# ACE.net
KiCad netlist of a schematic drawn in Altium Designer
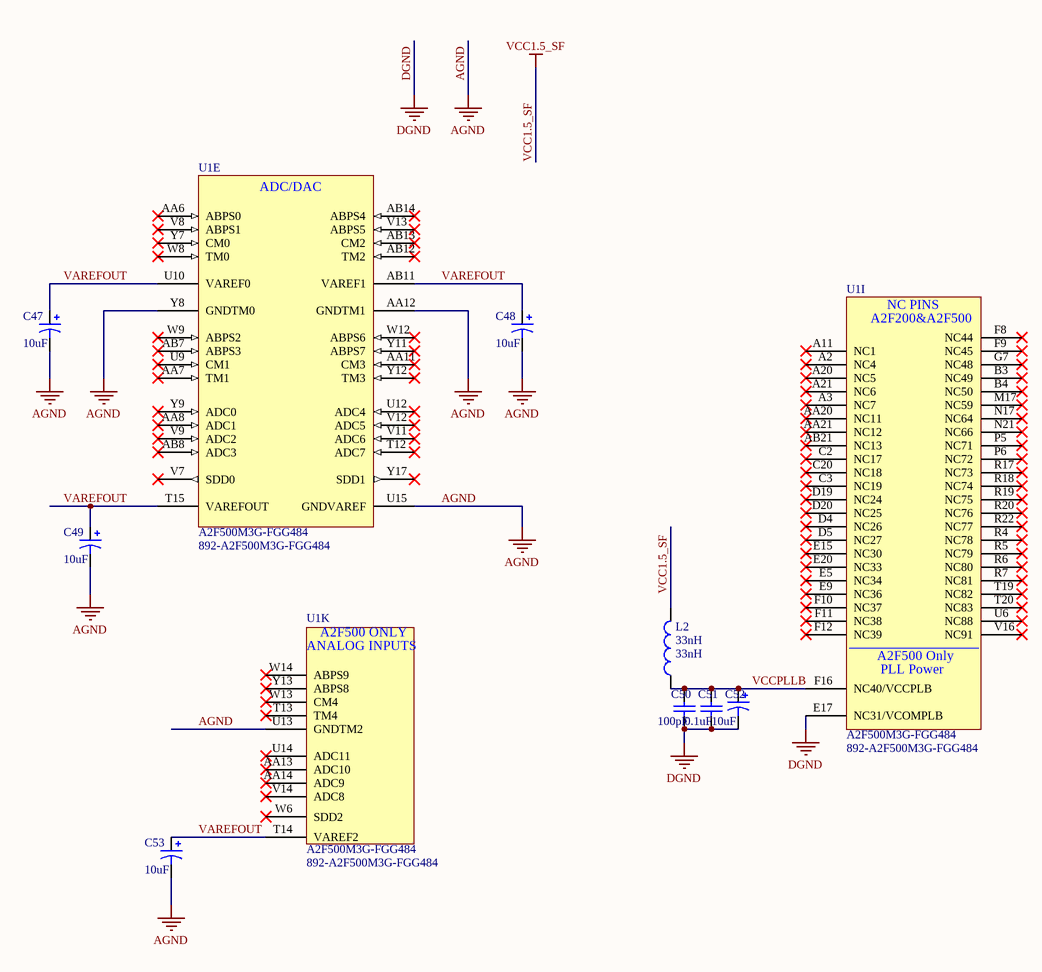
[diagram p0: ACE.SchDoc]

(export (version "E")
  (design (tool "Eeschema 10.0.6"))
  (components
    (comp (ref "C47")
      (value "10uF")
      (footprint "C0805")
      (description "Polarized Capacitor (Surface Mount)")
      (fields (field (name "PUBLISHER") "Altium Limited"))
      (libsource (lib "Miscellaneous Devices") (part "Cap Pol3"))
    )
    (comp (ref "C48")
      (value "10uF")
      (footprint "C0805")
      (description "Polarized Capacitor (Surface Mount)")
      (fields (field (name "PUBLISHER") "Altium Limited"))
      (libsource (lib "Miscellaneous Devices") (part "Cap Pol3"))
    )
    (comp (ref "C49")
      (value "10uF")
      (footprint "C0805")
      (description "Polarized Capacitor (Surface Mount)")
      (fields (field (name "PUBLISHER") "Altium Limited"))
      (libsource (lib "Miscellaneous Devices") (part "Cap Pol3"))
    )
    (comp (ref "C50")
      (value "100pF")
      (footprint "0402")
      (description "Capacitor (Semiconductor SIM Model)")
      (fields (field (name "PUBLISHER") "Altium Limited"))
      (libsource (lib "Miscellaneous Devices") (part "Cap Semi"))
    )
    (comp (ref "C51")
      (value "0.1uF")
      (footprint "0402")
      (description "Capacitor (Semiconductor SIM Model)")
      (fields (field (name "PUBLISHER") "Altium Limited"))
      (libsource (lib "Miscellaneous Devices") (part "Cap Semi"))
    )
    (comp (ref "C52")
      (value "10uF")
      (footprint "C0805")
      (description "Polarized Capacitor (Surface Mount)")
      (fields (field (name "PUBLISHER") "Altium Limited"))
      (libsource (lib "Miscellaneous Devices") (part "Cap Pol3"))
    )
    (comp (ref "C53")
      (value "10uF")
      (footprint "C0805")
      (description "Polarized Capacitor (Surface Mount)")
      (fields (field (name "PUBLISHER") "Altium Limited"))
      (libsource (lib "Miscellaneous Devices") (part "Cap Pol3"))
    )
    (comp (ref "L2")
      (value "33nH")
      (footprint "0402")
      (description "Inductor")
      (fields (field (name "ALTIUM_VALUE") "33nH") (field (name "PUBLISHER") "Altium Limited"))
      (libsource (lib "Miscellaneous Devices") (part "Inductor"))
    )
    (comp (ref "U1")
      (value "A2F500M3G-FGG484")
      (footprint "BGA100P22X22-484N")
      (description "FPGA - Field Programmable Gate Array 500K System Gates")
      (fields (field (name "SUPPLIER PART NUMBER 1") "892-A2F500M3G-FGG484"))
      (libsource (lib "SDR") (part "F2-200_500-FGG484_1"))
    )
  )
  (nets
    (net (code "1") (name "/VAREFOUT") (class "Default")
      (node (ref "C47") (pin "1") (pinfunction "1_1") (pintype "passive"))
      (node (ref "C48") (pin "1") (pinfunction "1_1") (pintype "passive"))
      (node (ref "C49") (pin "1") (pinfunction "1_1") (pintype "passive"))
      (node (ref "C53") (pin "1") (pinfunction "1_1") (pintype "passive"))
      (node (ref "U1") (pin "AB11") (pinfunction "VAREF1_AB11") (pintype "power_in"))
      (node (ref "U1") (pin "T14") (pinfunction "VAREF2_T14") (pintype "power_in"))
      (node (ref "U1") (pin "T15") (pinfunction "VAREFOUT_T15") (pintype "power_in"))
      (node (ref "U1") (pin "U10") (pinfunction "VAREF0_U10") (pintype "power_in"))
    )
    (net (code "2") (name "/VCCPLLB") (class "Default")
      (node (ref "C50") (pin "2") (pinfunction "2_2") (pintype "passive"))
      (node (ref "C51") (pin "2") (pinfunction "2_2") (pintype "passive"))
      (node (ref "C52") (pin "1") (pinfunction "1_1") (pintype "passive"))
      (node (ref "L2") (pin "1") (pinfunction "1_1") (pintype "passive"))
      (node (ref "U1") (pin "F16") (pinfunction "NC40/VCCPLB_F16") (pintype "power_in"))
    )
    (net (code "3") (name "AGND") (class "Default")
      (node (ref "C47") (pin "2") (pinfunction "2_2") (pintype "passive"))
      (node (ref "C48") (pin "2") (pinfunction "2_2") (pintype "passive"))
      (node (ref "C49") (pin "2") (pinfunction "2_2") (pintype "passive"))
      (node (ref "C53") (pin "2") (pinfunction "2_2") (pintype "passive"))
      (node (ref "U1") (pin "AA12") (pinfunction "GNDTM1_AA12") (pintype "power_in"))
      (node (ref "U1") (pin "U13") (pinfunction "GNDTM2_U13") (pintype "passive"))
      (node (ref "U1") (pin "U15") (pinfunction "GNDVAREF_U15") (pintype "power_in"))
      (node (ref "U1") (pin "Y8") (pinfunction "GNDTM0_Y8") (pintype "power_in"))
    )
    (net (code "4") (name "DGND") (class "Default")
      (node (ref "C50") (pin "1") (pinfunction "1_1") (pintype "passive"))
      (node (ref "C51") (pin "1") (pinfunction "1_1") (pintype "passive"))
      (node (ref "C52") (pin "2") (pinfunction "2_2") (pintype "passive"))
      (node (ref "U1") (pin "E17") (pinfunction "NC31/VCOMPLB_E17") (pintype "power_in"))
    )
    (net (code "5") (name "VCC1.5_SF") (class "Default")
      (node (ref "L2") (pin "2") (pinfunction "2_2") (pintype "passive"))
    )
    (net (code "6") (name "unconnected-(U1E-ABPS0-PadAA6)") (class "Default")
      (node (ref "U1") (pin "AA6") (pinfunction "ABPS0_AA6") (pintype "input+no_connect"))
    )
    (net (code "7") (name "unconnected-(U1E-ABPS1-PadV8)") (class "Default")
      (node (ref "U1") (pin "V8") (pinfunction "ABPS1_V8") (pintype "input+no_connect"))
    )
    (net (code "8") (name "unconnected-(U1E-ABPS2-PadW9)") (class "Default")
      (node (ref "U1") (pin "W9") (pinfunction "ABPS2_W9") (pintype "input+no_connect"))
    )
    (net (code "9") (name "unconnected-(U1E-ABPS3-PadAB7)") (class "Default")
      (node (ref "U1") (pin "AB7") (pinfunction "ABPS3_AB7") (pintype "input+no_connect"))
    )
    (net (code "10") (name "unconnected-(U1E-ABPS4-PadAB14)") (class "Default")
      (node (ref "U1") (pin "AB14") (pinfunction "ABPS4_AB14") (pintype "input+no_connect"))
    )
    (net (code "11") (name "unconnected-(U1E-ABPS5-PadV13)") (class "Default")
      (node (ref "U1") (pin "V13") (pinfunction "ABPS5_V13") (pintype "input+no_connect"))
    )
    (net (code "12") (name "unconnected-(U1E-ABPS6-PadW12)") (class "Default")
      (node (ref "U1") (pin "W12") (pinfunction "ABPS6_W12") (pintype "input+no_connect"))
    )
    (net (code "13") (name "unconnected-(U1E-ABPS7-PadY11)") (class "Default")
      (node (ref "U1") (pin "Y11") (pinfunction "ABPS7_Y11") (pintype "input+no_connect"))
    )
    (net (code "14") (name "unconnected-(U1E-ADC0-PadY9)") (class "Default")
      (node (ref "U1") (pin "Y9") (pinfunction "ADC0_Y9") (pintype "input+no_connect"))
    )
    (net (code "15") (name "unconnected-(U1E-ADC1-PadAA8)") (class "Default")
      (node (ref "U1") (pin "AA8") (pinfunction "ADC1_AA8") (pintype "input+no_connect"))
    )
    (net (code "16") (name "unconnected-(U1E-ADC2-PadV9)") (class "Default")
      (node (ref "U1") (pin "V9") (pinfunction "ADC2_V9") (pintype "input+no_connect"))
    )
    (net (code "17") (name "unconnected-(U1E-ADC3-PadAB8)") (class "Default")
      (node (ref "U1") (pin "AB8") (pinfunction "ADC3_AB8") (pintype "input+no_connect"))
    )
    (net (code "18") (name "unconnected-(U1E-ADC4-PadU12)") (class "Default")
      (node (ref "U1") (pin "U12") (pinfunction "ADC4_U12") (pintype "input+no_connect"))
    )
    (net (code "19") (name "unconnected-(U1E-ADC5-PadV12)") (class "Default")
      (node (ref "U1") (pin "V12") (pinfunction "ADC5_V12") (pintype "input+no_connect"))
    )
    (net (code "20") (name "unconnected-(U1E-ADC6-PadV11)") (class "Default")
      (node (ref "U1") (pin "V11") (pinfunction "ADC6_V11") (pintype "input+no_connect"))
    )
    (net (code "21") (name "unconnected-(U1E-ADC7-PadT12)") (class "Default")
      (node (ref "U1") (pin "T12") (pinfunction "ADC7_T12") (pintype "input+no_connect"))
    )
    (net (code "22") (name "unconnected-(U1E-CM0-PadY7)") (class "Default")
      (node (ref "U1") (pin "Y7") (pinfunction "CM0_Y7") (pintype "input+no_connect"))
    )
    (net (code "23") (name "unconnected-(U1E-CM1-PadU9)") (class "Default")
      (node (ref "U1") (pin "U9") (pinfunction "CM1_U9") (pintype "input+no_connect"))
    )
    (net (code "24") (name "unconnected-(U1E-CM2-PadAB13)") (class "Default")
      (node (ref "U1") (pin "AB13") (pinfunction "CM2_AB13") (pintype "input+no_connect"))
    )
    (net (code "25") (name "unconnected-(U1E-CM3-PadAA11)") (class "Default")
      (node (ref "U1") (pin "AA11") (pinfunction "CM3_AA11") (pintype "input+no_connect"))
    )
    (net (code "26") (name "unconnected-(U1E-SDD0-PadV7)") (class "Default")
      (node (ref "U1") (pin "V7") (pinfunction "SDD0_V7") (pintype "output+no_connect"))
    )
    (net (code "27") (name "unconnected-(U1E-SDD1-PadY17)") (class "Default")
      (node (ref "U1") (pin "Y17") (pinfunction "SDD1_Y17") (pintype "output+no_connect"))
    )
    (net (code "28") (name "unconnected-(U1E-TM0-PadW8)") (class "Default")
      (node (ref "U1") (pin "W8") (pinfunction "TM0_W8") (pintype "input+no_connect"))
    )
    (net (code "29") (name "unconnected-(U1E-TM1-PadAA7)") (class "Default")
      (node (ref "U1") (pin "AA7") (pinfunction "TM1_AA7") (pintype "input+no_connect"))
    )
    (net (code "30") (name "unconnected-(U1E-TM2-PadAB12)") (class "Default")
      (node (ref "U1") (pin "AB12") (pinfunction "TM2_AB12") (pintype "input+no_connect"))
    )
    (net (code "31") (name "unconnected-(U1E-TM3-PadY12)") (class "Default")
      (node (ref "U1") (pin "Y12") (pinfunction "TM3_Y12") (pintype "input+no_connect"))
    )
    (net (code "32") (name "unconnected-(U1I-NC1-PadA11)") (class "Default")
      (node (ref "U1") (pin "A11") (pinfunction "NC1_A11") (pintype "passive+no_connect"))
    )
    (net (code "33") (name "unconnected-(U1I-NC4-PadA2)") (class "Default")
      (node (ref "U1") (pin "A2") (pinfunction "NC4_A2") (pintype "passive+no_connect"))
    )
    (net (code "34") (name "unconnected-(U1I-NC5-PadA20)") (class "Default")
      (node (ref "U1") (pin "A20") (pinfunction "NC5_A20") (pintype "passive+no_connect"))
    )
    (net (code "35") (name "unconnected-(U1I-NC6-PadA21)") (class "Default")
      (node (ref "U1") (pin "A21") (pinfunction "NC6_A21") (pintype "passive+no_connect"))
    )
    (net (code "36") (name "unconnected-(U1I-NC7-PadA3)") (class "Default")
      (node (ref "U1") (pin "A3") (pinfunction "NC7_A3") (pintype "passive+no_connect"))
    )
    (net (code "37") (name "unconnected-(U1I-NC11-PadAA20)") (class "Default")
      (node (ref "U1") (pin "AA20") (pinfunction "NC11_AA20") (pintype "passive+no_connect"))
    )
    (net (code "38") (name "unconnected-(U1I-NC12-PadAA21)") (class "Default")
      (node (ref "U1") (pin "AA21") (pinfunction "NC12_AA21") (pintype "passive+no_connect"))
    )
    (net (code "39") (name "unconnected-(U1I-NC13-PadAB21)") (class "Default")
      (node (ref "U1") (pin "AB21") (pinfunction "NC13_AB21") (pintype "passive+no_connect"))
    )
    (net (code "40") (name "unconnected-(U1I-NC17-PadC2)") (class "Default")
      (node (ref "U1") (pin "C2") (pinfunction "NC17_C2") (pintype "passive+no_connect"))
    )
    (net (code "41") (name "unconnected-(U1I-NC18-PadC20)") (class "Default")
      (node (ref "U1") (pin "C20") (pinfunction "NC18_C20") (pintype "passive+no_connect"))
    )
    (net (code "42") (name "unconnected-(U1I-NC19-PadC3)") (class "Default")
      (node (ref "U1") (pin "C3") (pinfunction "NC19_C3") (pintype "passive+no_connect"))
    )
    (net (code "43") (name "unconnected-(U1I-NC24-PadD19)") (class "Default")
      (node (ref "U1") (pin "D19") (pinfunction "NC24_D19") (pintype "passive+no_connect"))
    )
    (net (code "44") (name "unconnected-(U1I-NC25-PadD20)") (class "Default")
      (node (ref "U1") (pin "D20") (pinfunction "NC25_D20") (pintype "passive+no_connect"))
    )
    (net (code "45") (name "unconnected-(U1I-NC26-PadD4)") (class "Default")
      (node (ref "U1") (pin "D4") (pinfunction "NC26_D4") (pintype "passive+no_connect"))
    )
    (net (code "46") (name "unconnected-(U1I-NC27-PadD5)") (class "Default")
      (node (ref "U1") (pin "D5") (pinfunction "NC27_D5") (pintype "passive+no_connect"))
    )
    (net (code "47") (name "unconnected-(U1I-NC30-PadE15)") (class "Default")
      (node (ref "U1") (pin "E15") (pinfunction "NC30_E15") (pintype "passive+no_connect"))
    )
    (net (code "48") (name "unconnected-(U1I-NC33-PadE20)") (class "Default")
      (node (ref "U1") (pin "E20") (pinfunction "NC33_E20") (pintype "passive+no_connect"))
    )
    (net (code "49") (name "unconnected-(U1I-NC34-PadE5)") (class "Default")
      (node (ref "U1") (pin "E5") (pinfunction "NC34_E5") (pintype "passive+no_connect"))
    )
    (net (code "50") (name "unconnected-(U1I-NC36-PadE9)") (class "Default")
      (node (ref "U1") (pin "E9") (pinfunction "NC36_E9") (pintype "passive+no_connect"))
    )
    (net (code "51") (name "unconnected-(U1I-NC37-PadF10)") (class "Default")
      (node (ref "U1") (pin "F10") (pinfunction "NC37_F10") (pintype "passive+no_connect"))
    )
    (net (code "52") (name "unconnected-(U1I-NC38-PadF11)") (class "Default")
      (node (ref "U1") (pin "F11") (pinfunction "NC38_F11") (pintype "passive+no_connect"))
    )
    (net (code "53") (name "unconnected-(U1I-NC39-PadF12)") (class "Default")
      (node (ref "U1") (pin "F12") (pinfunction "NC39_F12") (pintype "passive+no_connect"))
    )
    (net (code "54") (name "unconnected-(U1I-NC44-PadF8)") (class "Default")
      (node (ref "U1") (pin "F8") (pinfunction "NC44_F8") (pintype "passive+no_connect"))
    )
    (net (code "55") (name "unconnected-(U1I-NC45-PadF9)") (class "Default")
      (node (ref "U1") (pin "F9") (pinfunction "NC45_F9") (pintype "passive+no_connect"))
    )
    (net (code "56") (name "unconnected-(U1I-NC48-PadG7)") (class "Default")
      (node (ref "U1") (pin "G7") (pinfunction "NC48_G7") (pintype "passive+no_connect"))
    )
    (net (code "57") (name "unconnected-(U1I-NC49-PadB3)") (class "Default")
      (node (ref "U1") (pin "B3") (pinfunction "NC49_B3") (pintype "passive+no_connect"))
    )
    (net (code "58") (name "unconnected-(U1I-NC50-PadB4)") (class "Default")
      (node (ref "U1") (pin "B4") (pinfunction "NC50_B4") (pintype "passive+no_connect"))
    )
    (net (code "59") (name "unconnected-(U1I-NC59-PadM17)") (class "Default")
      (node (ref "U1") (pin "M17") (pinfunction "NC59_M17") (pintype "passive+no_connect"))
    )
    (net (code "60") (name "unconnected-(U1I-NC64-PadN17)") (class "Default")
      (node (ref "U1") (pin "N17") (pinfunction "NC64_N17") (pintype "passive+no_connect"))
    )
    (net (code "61") (name "unconnected-(U1I-NC66-PadN21)") (class "Default")
      (node (ref "U1") (pin "N21") (pinfunction "NC66_N21") (pintype "passive+no_connect"))
    )
    (net (code "62") (name "unconnected-(U1I-NC71-PadP5)") (class "Default")
      (node (ref "U1") (pin "P5") (pinfunction "NC71_P5") (pintype "passive+no_connect"))
    )
    (net (code "63") (name "unconnected-(U1I-NC72-PadP6)") (class "Default")
      (node (ref "U1") (pin "P6") (pinfunction "NC72_P6") (pintype "passive+no_connect"))
    )
    (net (code "64") (name "unconnected-(U1I-NC73-PadR17)") (class "Default")
      (node (ref "U1") (pin "R17") (pinfunction "NC73_R17") (pintype "passive+no_connect"))
    )
    (net (code "65") (name "unconnected-(U1I-NC74-PadR18)") (class "Default")
      (node (ref "U1") (pin "R18") (pinfunction "NC74_R18") (pintype "passive+no_connect"))
    )
    (net (code "66") (name "unconnected-(U1I-NC75-PadR19)") (class "Default")
      (node (ref "U1") (pin "R19") (pinfunction "NC75_R19") (pintype "passive+no_connect"))
    )
    (net (code "67") (name "unconnected-(U1I-NC76-PadR20)") (class "Default")
      (node (ref "U1") (pin "R20") (pinfunction "NC76_R20") (pintype "passive+no_connect"))
    )
    (net (code "68") (name "unconnected-(U1I-NC77-PadR22)") (class "Default")
      (node (ref "U1") (pin "R22") (pinfunction "NC77_R22") (pintype "passive+no_connect"))
    )
    (net (code "69") (name "unconnected-(U1I-NC78-PadR4)") (class "Default")
      (node (ref "U1") (pin "R4") (pinfunction "NC78_R4") (pintype "passive+no_connect"))
    )
    (net (code "70") (name "unconnected-(U1I-NC79-PadR5)") (class "Default")
      (node (ref "U1") (pin "R5") (pinfunction "NC79_R5") (pintype "passive+no_connect"))
    )
    (net (code "71") (name "unconnected-(U1I-NC80-PadR6)") (class "Default")
      (node (ref "U1") (pin "R6") (pinfunction "NC80_R6") (pintype "passive+no_connect"))
    )
    (net (code "72") (name "unconnected-(U1I-NC81-PadR7)") (class "Default")
      (node (ref "U1") (pin "R7") (pinfunction "NC81_R7") (pintype "passive+no_connect"))
    )
    (net (code "73") (name "unconnected-(U1I-NC82-PadT19)") (class "Default")
      (node (ref "U1") (pin "T19") (pinfunction "NC82_T19") (pintype "passive+no_connect"))
    )
    (net (code "74") (name "unconnected-(U1I-NC83-PadT20)") (class "Default")
      (node (ref "U1") (pin "T20") (pinfunction "NC83_T20") (pintype "passive+no_connect"))
    )
    (net (code "75") (name "unconnected-(U1I-NC88-PadU6)") (class "Default")
      (node (ref "U1") (pin "U6") (pinfunction "NC88_U6") (pintype "passive+no_connect"))
    )
    (net (code "76") (name "unconnected-(U1I-NC91-PadV16)") (class "Default")
      (node (ref "U1") (pin "V16") (pinfunction "NC91_V16") (pintype "passive+no_connect"))
    )
    (net (code "77") (name "unconnected-(U1K-ABPS8-PadY13)") (class "Default")
      (node (ref "U1") (pin "Y13") (pinfunction "ABPS8_Y13") (pintype "passive+no_connect"))
    )
    (net (code "78") (name "unconnected-(U1K-ABPS9-PadW14)") (class "Default")
      (node (ref "U1") (pin "W14") (pinfunction "ABPS9_W14") (pintype "passive+no_connect"))
    )
    (net (code "79") (name "unconnected-(U1K-ADC8-PadV14)") (class "Default")
      (node (ref "U1") (pin "V14") (pinfunction "ADC8_V14") (pintype "passive+no_connect"))
    )
    (net (code "80") (name "unconnected-(U1K-ADC9-PadAA14)") (class "Default")
      (node (ref "U1") (pin "AA14") (pinfunction "ADC9_AA14") (pintype "passive+no_connect"))
    )
    (net (code "81") (name "unconnected-(U1K-ADC10-PadAA13)") (class "Default")
      (node (ref "U1") (pin "AA13") (pinfunction "ADC10_AA13") (pintype "passive+no_connect"))
    )
    (net (code "82") (name "unconnected-(U1K-ADC11-PadU14)") (class "Default")
      (node (ref "U1") (pin "U14") (pinfunction "ADC11_U14") (pintype "passive+no_connect"))
    )
    (net (code "83") (name "unconnected-(U1K-CM4-PadW13)") (class "Default")
      (node (ref "U1") (pin "W13") (pinfunction "CM4_W13") (pintype "passive+no_connect"))
    )
    (net (code "84") (name "unconnected-(U1K-SDD2-PadW6)") (class "Default")
      (node (ref "U1") (pin "W6") (pinfunction "SDD2_W6") (pintype "passive+no_connect"))
    )
    (net (code "85") (name "unconnected-(U1K-TM4-PadT13)") (class "Default")
      (node (ref "U1") (pin "T13") (pinfunction "TM4_T13") (pintype "passive+no_connect"))
    )
  )
)
